# ESP-12E_Dev_Board.net
KiCad netlist of a schematic drawn in EAGLE
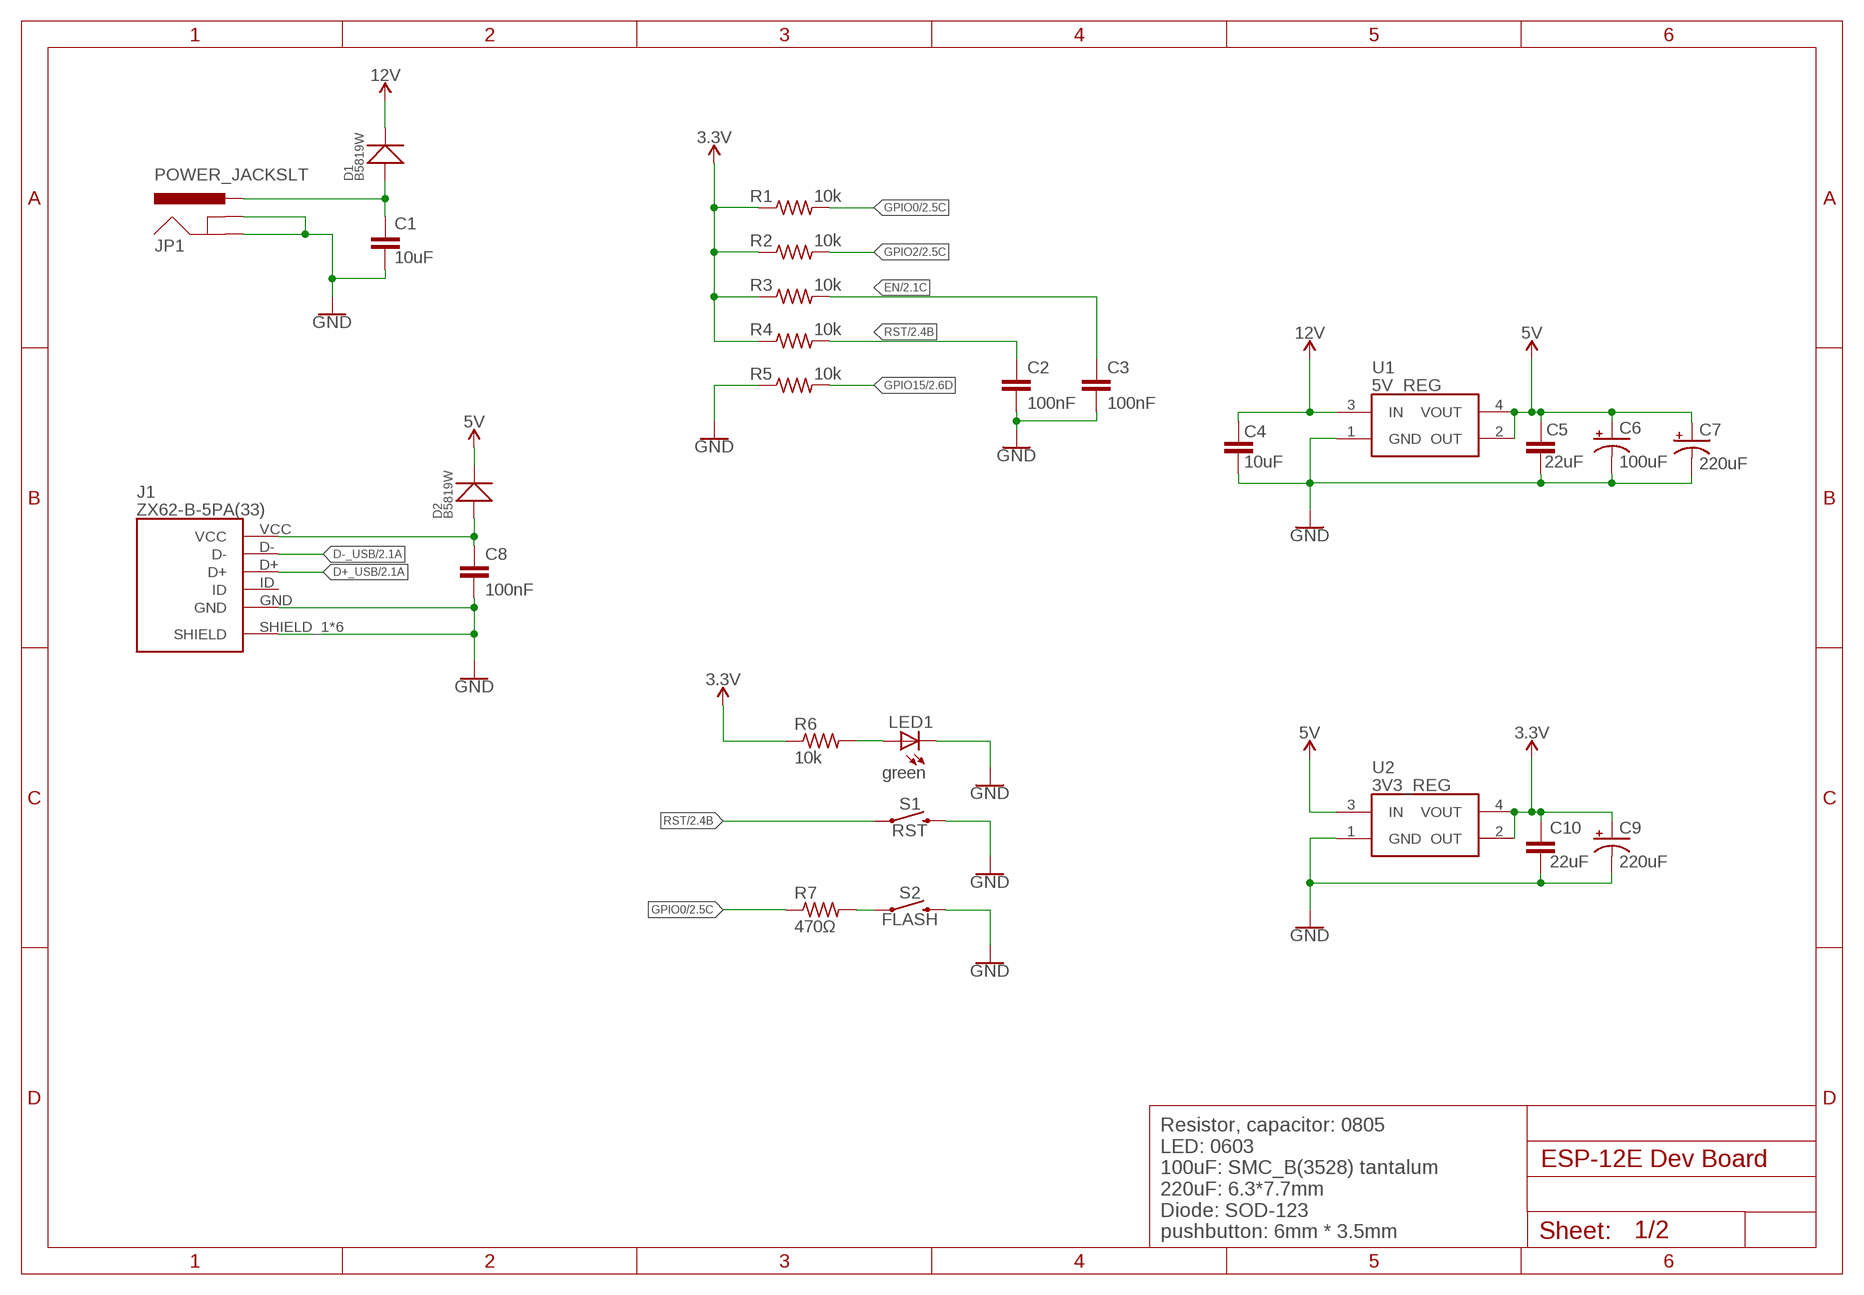
[diagram p0: schematic, sheet 1]
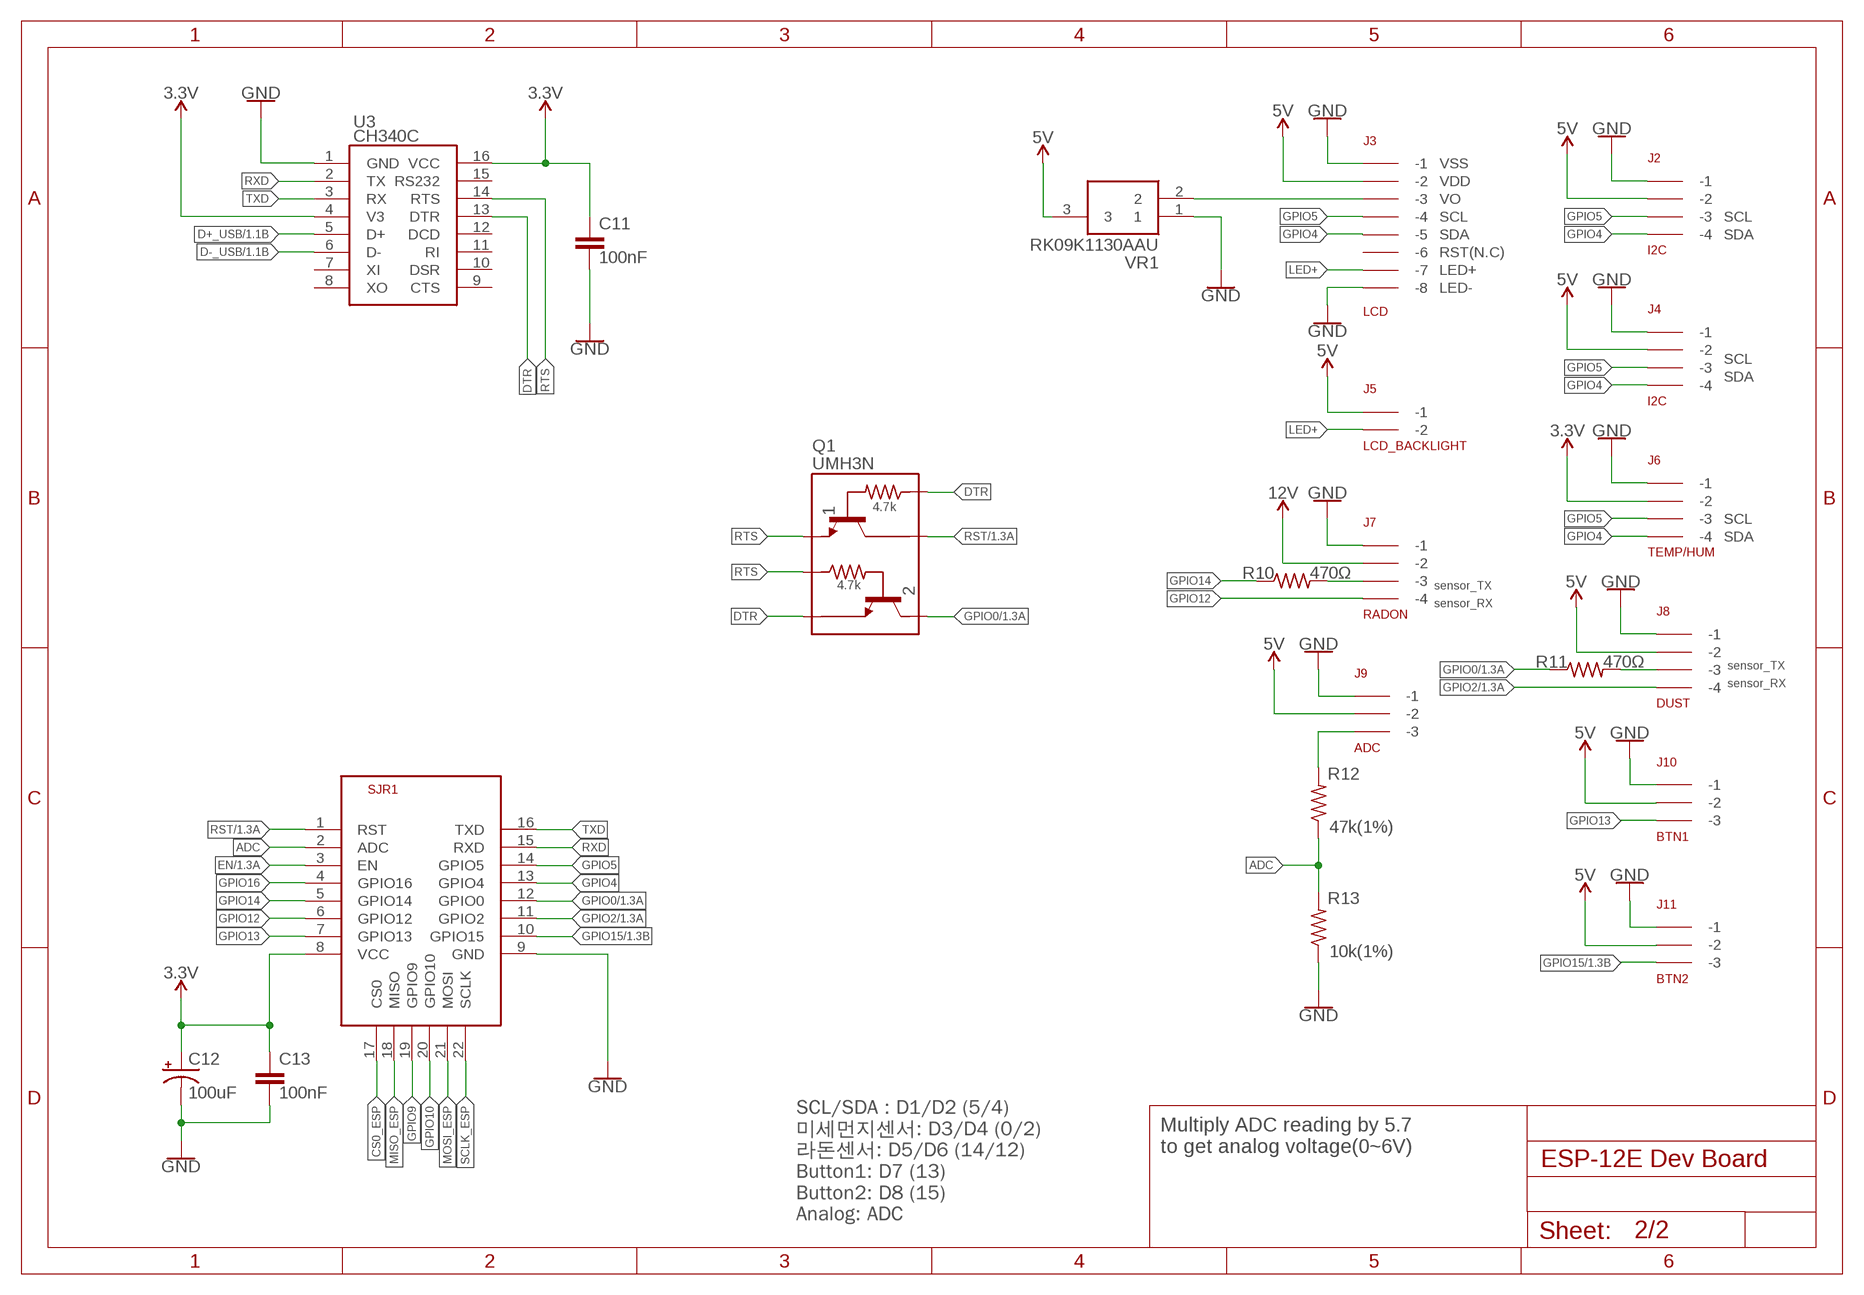
[diagram p1: schematic, sheet 2]

(export (version "E")
  (design (tool "Eeschema 10.0.6"))
  (components
    (comp (ref "C1")
      (value "10uF")
      (footprint "eagle-import:C0805")
      (libsource (lib "eagle-import") (part "C-EUC0805"))
    )
    (comp (ref "C2")
      (value "100nF")
      (footprint "eagle-import:C0805")
      (libsource (lib "eagle-import") (part "C-EUC0805"))
    )
    (comp (ref "C3")
      (value "100nF")
      (footprint "eagle-import:C0805")
      (libsource (lib "eagle-import") (part "C-EUC0805"))
    )
    (comp (ref "C4")
      (value "10uF")
      (footprint "eagle-import:C0805")
      (libsource (lib "eagle-import") (part "C-EUC0805"))
    )
    (comp (ref "C5")
      (value "22uF")
      (footprint "eagle-import:C0805")
      (libsource (lib "eagle-import") (part "C-EUC0805"))
    )
    (comp (ref "C6")
      (value "100uF")
      (footprint "eagle-import:SMC_B")
      (libsource (lib "eagle-import") (part "CPOL-USSMCB"))
    )
    (comp (ref "C7")
      (value "220uF")
      (footprint "eagle-import:UD-6,3X7,7_NICHICON")
      (libsource (lib "eagle-import") (part "CPOL-USUD-6,3X7,7"))
    )
    (comp (ref "C8")
      (value "100nF")
      (footprint "eagle-import:C0805")
      (libsource (lib "eagle-import") (part "C-EUC0805"))
    )
    (comp (ref "C9")
      (value "220uF")
      (footprint "eagle-import:UD-6,3X7,7_NICHICON")
      (libsource (lib "eagle-import") (part "CPOL-USUD-6,3X7,7"))
    )
    (comp (ref "C10")
      (value "22uF")
      (footprint "eagle-import:C0805")
      (libsource (lib "eagle-import") (part "C-EUC0805"))
    )
    (comp (ref "D1")
      (value "B5819W")
      (footprint "eagle-import:SOD-123")
      (fields (field (name "MPN") "SS0520-7-F"))
      (libsource (lib "eagle-import") (part "SMD-DIODE-SCHOTTKY-20V-500MA(SOD-123)"))
    )
    (comp (ref "D2")
      (value "B5819W")
      (footprint "eagle-import:SOD-123")
      (fields (field (name "MPN") "SS0520-7-F"))
      (libsource (lib "eagle-import") (part "SMD-DIODE-SCHOTTKY-20V-500MA(SOD-123)"))
    )
    (comp (ref "J1")
      (value "ZX62-B-5PA(33)")
      (footprint "eagle-import:ZX62B5PA33")
      (fields (field (name "MOUSER_PART_NUMBER") "798-ZX62-B-5PA33"))
      (libsource (lib "eagle-import") (part "ZX62-B-5PA(33)"))
    )
    (comp (ref "JP1")
      (value "POWER_JACKSLT")
      (footprint "eagle-import:POWER_JACK_SLOT")
      (libsource (lib "eagle-import") (part "POWER_JACKSLT"))
    )
    (comp (ref "LED1")
      (value "green")
      (footprint "eagle-import:CHIP-LED0603")
      (libsource (lib "eagle-import") (part "LEDCHIP-LED0603"))
    )
    (comp (ref "R1")
      (value "10k")
      (footprint "eagle-import:R0805")
      (libsource (lib "eagle-import") (part "R-US_R0805"))
    )
    (comp (ref "R2")
      (value "10k")
      (footprint "eagle-import:R0805")
      (libsource (lib "eagle-import") (part "R-US_R0805"))
    )
    (comp (ref "R3")
      (value "10k")
      (footprint "eagle-import:R0805")
      (libsource (lib "eagle-import") (part "R-US_R0805"))
    )
    (comp (ref "R4")
      (value "10k")
      (footprint "eagle-import:R0805")
      (libsource (lib "eagle-import") (part "R-US_R0805"))
    )
    (comp (ref "R5")
      (value "10k")
      (footprint "eagle-import:R0805")
      (libsource (lib "eagle-import") (part "R-US_R0805"))
    )
    (comp (ref "R6")
      (value "10k")
      (footprint "eagle-import:R0805")
      (libsource (lib "eagle-import") (part "R-US_R0805"))
    )
    (comp (ref "R7")
      (value "470Ω")
      (footprint "eagle-import:R0805")
      (libsource (lib "eagle-import") (part "R-US_R0805"))
    )
    (comp (ref "S1")
      (value "RST")
      (footprint "eagle-import:TACTILE_SWITCH_SMD_6.0X3.5MM")
      (libsource (lib "eagle-import") (part "MOMENTARY-SWITCH-SPST-SMD-6.0X3.5MM"))
    )
    (comp (ref "S2")
      (value "FLASH")
      (footprint "eagle-import:TACTILE_SWITCH_SMD_6.0X3.5MM")
      (libsource (lib "eagle-import") (part "MOMENTARY-SWITCH-SPST-SMD-6.0X3.5MM"))
    )
    (comp (ref "U1")
      (value "5V_REG")
      (footprint "eagle-import:SOT230P700X170-4N")
      (fields
        (field (name "MANUFACTURER_PART_NUMBER") "AZ1117H-5.0TRE1")
        (field (name "MOUSER_PART_NUMBER") "621-AZ1117H-5.0TRE1")
      )
      (libsource (lib "eagle-import") (part "AZ1117H-5.0TRE1"))
    )
    (comp (ref "U2")
      (value "3V3_REG")
      (footprint "eagle-import:SOT230P700X170-4N")
      (fields
        (field (name "MANUFACTURER_PART_NUMBER") "AZ1117H-5.0TRE1")
        (field (name "MOUSER_PART_NUMBER") "621-AZ1117H-5.0TRE1")
      )
      (libsource (lib "eagle-import") (part "AZ1117H-5.0TRE1"))
    )
    (comp (ref "C11")
      (value "100nF")
      (footprint "eagle-import:C0805")
      (libsource (lib "eagle-import") (part "C-EUC0805"))
    )
    (comp (ref "C12")
      (value "100uF")
      (footprint "eagle-import:SMC_B")
      (libsource (lib "eagle-import") (part "CPOL-USSMCB"))
    )
    (comp (ref "C13")
      (value "100nF")
      (footprint "eagle-import:C0805")
      (libsource (lib "eagle-import") (part "C-EUC0805"))
    )
    (comp (ref "J2")
      (value "I2C")
      (footprint "eagle-import:5267-4")
      (libsource (lib "eagle-import") (part "5267-4"))
    )
    (comp (ref "J3")
      (value "LCD")
      (footprint "eagle-import:5267-8")
      (libsource (lib "eagle-import") (part "5267-8"))
    )
    (comp (ref "J4")
      (value "I2C")
      (footprint "eagle-import:5267-4")
      (libsource (lib "eagle-import") (part "5267-4"))
    )
    (comp (ref "J5")
      (value "LCD_BACKLIGHT")
      (footprint "eagle-import:5267-2")
      (libsource (lib "eagle-import") (part "5267-2"))
    )
    (comp (ref "J6")
      (value "TEMP/HUM")
      (footprint "eagle-import:5267-4")
      (libsource (lib "eagle-import") (part "5267-4"))
    )
    (comp (ref "J7")
      (value "RADON")
      (footprint "eagle-import:5267-4")
      (libsource (lib "eagle-import") (part "5267-4"))
    )
    (comp (ref "J8")
      (value "DUST")
      (footprint "eagle-import:5267-4")
      (libsource (lib "eagle-import") (part "5267-4"))
    )
    (comp (ref "J9")
      (value "ADC")
      (footprint "eagle-import:5267-3")
      (libsource (lib "eagle-import") (part "5267-3"))
    )
    (comp (ref "J10")
      (value "BTN1")
      (footprint "eagle-import:5267-3")
      (libsource (lib "eagle-import") (part "5267-3"))
    )
    (comp (ref "J11")
      (value "BTN2")
      (footprint "eagle-import:5267-3")
      (libsource (lib "eagle-import") (part "5267-3"))
    )
    (comp (ref "Q1")
      (value "UMH3N")
      (footprint "eagle-import:SOT65P210X100-6N")
      (fields
        (field (name "MANUFACTURER_PART_NUMBER") "UMH3NFHATN")
        (field (name "MOUSER_PART_NUMBER") "755-UMH3NFHATN")
      )
      (libsource (lib "eagle-import") (part "UMH3NFHATN"))
    )
    (comp (ref "R10")
      (value "470Ω")
      (footprint "eagle-import:R0805")
      (libsource (lib "eagle-import") (part "R-US_R0805"))
    )
    (comp (ref "R11")
      (value "470Ω")
      (footprint "eagle-import:R0805")
      (libsource (lib "eagle-import") (part "R-US_R0805"))
    )
    (comp (ref "R12")
      (value "47k(1%)")
      (footprint "eagle-import:R0805")
      (libsource (lib "eagle-import") (part "R-US_R0805"))
    )
    (comp (ref "R13")
      (value "10k(1%)")
      (footprint "eagle-import:R0805")
      (libsource (lib "eagle-import") (part "R-US_R0805"))
    )
    (comp (ref "SJR1")
      (value "ESP-12E")
      (footprint "eagle-import:ESP8266-ESP12E")
      (libsource (lib "eagle-import") (part "ESP8266-12EESP12E"))
    )
    (comp (ref "U3")
      (value "CH340C")
      (footprint "eagle-import:SOIC16")
      (libsource (lib "eagle-import") (part "CH340G"))
    )
    (comp (ref "VR1")
      (value "RK09K1130AAU")
      (footprint "eagle-import:RK09K1130BGM")
      (fields
        (field (name "MANUFACTURER_PART_NUMBER") "RK09K1130A6S")
        (field (name "MOUSER_PART_NUMBER") "688-RK09K1130A6S")
      )
      (libsource (lib "eagle-import") (part "RK09K1130A6S"))
    )
  )
  (nets
    (net (code "1") (name "3.3V") (class "Default")
      (node (ref "C10") (pin "2") (pinfunction "2_2") (pintype "passive"))
      (node (ref "C11") (pin "2") (pinfunction "2_2") (pintype "passive"))
      (node (ref "C12") (pin "+") (pinfunction "+_+") (pintype "passive"))
      (node (ref "C13") (pin "2") (pinfunction "2_2") (pintype "passive"))
      (node (ref "C9") (pin "+") (pinfunction "+_+") (pintype "passive"))
      (node (ref "J6") (pin "P$2") (pinfunction "-2_P$2") (pintype "bidirectional"))
      (node (ref "R1") (pin "1") (pinfunction "1_1") (pintype "passive"))
      (node (ref "R2") (pin "1") (pinfunction "1_1") (pintype "passive"))
      (node (ref "R3") (pin "1") (pinfunction "1_1") (pintype "passive"))
      (node (ref "R4") (pin "1") (pinfunction "1_1") (pintype "passive"))
      (node (ref "R6") (pin "1") (pinfunction "1_1") (pintype "passive"))
      (node (ref "SJR1") (pin "8") (pinfunction "VCC_8") (pintype "bidirectional"))
      (node (ref "U2") (pin "2") (pinfunction "OUT_2") (pintype "bidirectional"))
      (node (ref "U2") (pin "4") (pinfunction "VOUT_4") (pintype "bidirectional"))
      (node (ref "U3") (pin "16") (pinfunction "VCC_16") (pintype "bidirectional"))
      (node (ref "U3") (pin "4") (pinfunction "V3_4") (pintype "bidirectional"))
    )
    (net (code "2") (name "5V") (class "Default")
      (node (ref "C5") (pin "1") (pinfunction "1_1") (pintype "passive"))
      (node (ref "C6") (pin "+") (pinfunction "+_+") (pintype "passive"))
      (node (ref "C7") (pin "+") (pinfunction "+_+") (pintype "passive"))
      (node (ref "D2") (pin "-") (pinfunction "-_-") (pintype "passive"))
      (node (ref "J10") (pin "P$2") (pinfunction "-2_P$2") (pintype "bidirectional"))
      (node (ref "J11") (pin "P$2") (pinfunction "-2_P$2") (pintype "bidirectional"))
      (node (ref "J2") (pin "P$2") (pinfunction "-2_P$2") (pintype "bidirectional"))
      (node (ref "J3") (pin "P$2") (pinfunction "-2_P$2") (pintype "bidirectional"))
      (node (ref "J4") (pin "P$2") (pinfunction "-2_P$2") (pintype "bidirectional"))
      (node (ref "J5") (pin "P$1") (pinfunction "-1_P$1") (pintype "bidirectional"))
      (node (ref "J8") (pin "P$2") (pinfunction "-2_P$2") (pintype "bidirectional"))
      (node (ref "J9") (pin "P$2") (pinfunction "-2_P$2") (pintype "bidirectional"))
      (node (ref "U1") (pin "2") (pinfunction "OUT_2") (pintype "bidirectional"))
      (node (ref "U1") (pin "4") (pinfunction "VOUT_4") (pintype "bidirectional"))
      (node (ref "U2") (pin "3") (pinfunction "IN_3") (pintype "bidirectional"))
      (node (ref "VR1") (pin "3") (pinfunction "3_3") (pintype "bidirectional"))
    )
    (net (code "3") (name "12V") (class "Default")
      (node (ref "C4") (pin "1") (pinfunction "1_1") (pintype "passive"))
      (node (ref "D1") (pin "-") (pinfunction "-_-") (pintype "passive"))
      (node (ref "J7") (pin "P$2") (pinfunction "-2_P$2") (pintype "bidirectional"))
      (node (ref "U1") (pin "3") (pinfunction "IN_3") (pintype "bidirectional"))
    )
    (net (code "4") (name "ADC") (class "Default")
      (node (ref "R12") (pin "1") (pinfunction "1_1") (pintype "passive"))
      (node (ref "R13") (pin "2") (pinfunction "2_2") (pintype "passive"))
      (node (ref "SJR1") (pin "2") (pinfunction "ADC_2") (pintype "bidirectional"))
    )
    (net (code "5") (name "CS0_ESP") (class "Default")
      (node (ref "SJR1") (pin "17") (pinfunction "CS0_17") (pintype "bidirectional"))
    )
    (net (code "6") (name "D+_USB") (class "Default")
      (node (ref "J1") (pin "D+") (pinfunction "D+_D+") (pintype "bidirectional"))
      (node (ref "U3") (pin "5") (pinfunction "D+_5") (pintype "bidirectional"))
    )
    (net (code "7") (name "D-_USB") (class "Default")
      (node (ref "J1") (pin "D-") (pinfunction "D-_D-") (pintype "bidirectional"))
      (node (ref "U3") (pin "6") (pinfunction "D-_6") (pintype "bidirectional"))
    )
    (net (code "8") (name "DTR") (class "Default")
      (node (ref "Q1") (pin "2") (pinfunction "2_2") (pintype "bidirectional"))
      (node (ref "Q1") (pin "4") (pinfunction "4_4") (pintype "bidirectional"))
      (node (ref "U3") (pin "13") (pinfunction "DTR_13") (pintype "bidirectional"))
    )
    (net (code "9") (name "EN") (class "Default")
      (node (ref "C3") (pin "2") (pinfunction "2_2") (pintype "passive"))
      (node (ref "R3") (pin "2") (pinfunction "2_2") (pintype "passive"))
      (node (ref "SJR1") (pin "3") (pinfunction "EN_3") (pintype "bidirectional"))
    )
    (net (code "10") (name "GND") (class "Default")
      (node (ref "C1") (pin "1") (pinfunction "1_1") (pintype "passive"))
      (node (ref "C10") (pin "1") (pinfunction "1_1") (pintype "passive"))
      (node (ref "C11") (pin "1") (pinfunction "1_1") (pintype "passive"))
      (node (ref "C12") (pin "-") (pinfunction "-_-") (pintype "passive"))
      (node (ref "C13") (pin "1") (pinfunction "1_1") (pintype "passive"))
      (node (ref "C2") (pin "1") (pinfunction "1_1") (pintype "passive"))
      (node (ref "C3") (pin "1") (pinfunction "1_1") (pintype "passive"))
      (node (ref "C4") (pin "2") (pinfunction "2_2") (pintype "passive"))
      (node (ref "C5") (pin "2") (pinfunction "2_2") (pintype "passive"))
      (node (ref "C6") (pin "-") (pinfunction "-_-") (pintype "passive"))
      (node (ref "C7") (pin "-") (pinfunction "-_-") (pintype "passive"))
      (node (ref "C8") (pin "1") (pinfunction "1_1") (pintype "passive"))
      (node (ref "C9") (pin "-") (pinfunction "-_-") (pintype "passive"))
      (node (ref "J1") (pin "GND") (pinfunction "GND_GND") (pintype "bidirectional"))
      (node (ref "J1") (pin "SHIELD_1") (pinfunction "SHIELD_SHIELD_1") (pintype "bidirectional"))
      (node (ref "J1") (pin "SHIELD_2") (pinfunction "SHIELD_SHIELD_2") (pintype "bidirectional"))
      (node (ref "J1") (pin "SHIELD_3") (pinfunction "SHIELD_SHIELD_3") (pintype "bidirectional"))
      (node (ref "J1") (pin "SHIELD_4") (pinfunction "SHIELD_SHIELD_4") (pintype "bidirectional"))
      (node (ref "J1") (pin "SHIELD_5") (pinfunction "SHIELD_SHIELD_5") (pintype "bidirectional"))
      (node (ref "J1") (pin "SHIELD_6") (pinfunction "SHIELD_SHIELD_6") (pintype "bidirectional"))
      (node (ref "J10") (pin "P$1") (pinfunction "-1_P$1") (pintype "bidirectional"))
      (node (ref "J11") (pin "P$1") (pinfunction "-1_P$1") (pintype "bidirectional"))
      (node (ref "J2") (pin "P$1") (pinfunction "-1_P$1") (pintype "bidirectional"))
      (node (ref "J3") (pin "P$1") (pinfunction "-1_P$1") (pintype "bidirectional"))
      (node (ref "J3") (pin "P$8") (pinfunction "-8_P$8") (pintype "bidirectional"))
      (node (ref "J4") (pin "P$1") (pinfunction "-1_P$1") (pintype "bidirectional"))
      (node (ref "J6") (pin "P$1") (pinfunction "-1_P$1") (pintype "bidirectional"))
      (node (ref "J7") (pin "P$1") (pinfunction "-1_P$1") (pintype "bidirectional"))
      (node (ref "J8") (pin "P$1") (pinfunction "-1_P$1") (pintype "bidirectional"))
      (node (ref "J9") (pin "P$1") (pinfunction "-1_P$1") (pintype "bidirectional"))
      (node (ref "JP1") (pin "GND@1") (pinfunction "GNDBREAK_GND@1") (pintype "power_in"))
      (node (ref "JP1") (pin "GND@2") (pinfunction "GND_GND@2") (pintype "power_in"))
      (node (ref "LED1") (pin "C") (pinfunction "C_C") (pintype "passive"))
      (node (ref "R13") (pin "1") (pinfunction "1_1") (pintype "passive"))
      (node (ref "R5") (pin "1") (pinfunction "1_1") (pintype "passive"))
      (node (ref "S1") (pin "2") (pinfunction "2_2") (pintype "passive"))
      (node (ref "S2") (pin "2") (pinfunction "2_2") (pintype "passive"))
      (node (ref "SJR1") (pin "9") (pinfunction "GND_9") (pintype "bidirectional"))
      (node (ref "U1") (pin "1") (pinfunction "GND_1") (pintype "bidirectional"))
      (node (ref "U2") (pin "1") (pinfunction "GND_1") (pintype "bidirectional"))
      (node (ref "U3") (pin "1") (pinfunction "GND_1") (pintype "bidirectional"))
      (node (ref "VR1") (pin "1") (pinfunction "1_1") (pintype "bidirectional"))
    )
    (net (code "11") (name "GPIO0") (class "Default")
      (node (ref "Q1") (pin "3") (pinfunction "3_3") (pintype "bidirectional"))
      (node (ref "R1") (pin "2") (pinfunction "2_2") (pintype "passive"))
      (node (ref "R11") (pin "1") (pinfunction "1_1") (pintype "passive"))
      (node (ref "R7") (pin "1") (pinfunction "1_1") (pintype "passive"))
      (node (ref "SJR1") (pin "12") (pinfunction "GPIO0_12") (pintype "bidirectional"))
    )
    (net (code "12") (name "GPIO2") (class "Default")
      (node (ref "J8") (pin "P$4") (pinfunction "-4_P$4") (pintype "bidirectional"))
      (node (ref "R2") (pin "2") (pinfunction "2_2") (pintype "passive"))
      (node (ref "SJR1") (pin "11") (pinfunction "GPIO2_11") (pintype "bidirectional"))
    )
    (net (code "13") (name "GPIO4") (class "Default")
      (node (ref "J2") (pin "P$4") (pinfunction "-4_P$4") (pintype "bidirectional"))
      (node (ref "J3") (pin "P$5") (pinfunction "-5_P$5") (pintype "bidirectional"))
      (node (ref "J4") (pin "P$4") (pinfunction "-4_P$4") (pintype "bidirectional"))
      (node (ref "J6") (pin "P$4") (pinfunction "-4_P$4") (pintype "bidirectional"))
      (node (ref "SJR1") (pin "13") (pinfunction "GPIO4_13") (pintype "bidirectional"))
    )
    (net (code "14") (name "GPIO5") (class "Default")
      (node (ref "J2") (pin "P$3") (pinfunction "-3_P$3") (pintype "bidirectional"))
      (node (ref "J3") (pin "P$4") (pinfunction "-4_P$4") (pintype "bidirectional"))
      (node (ref "J4") (pin "P$3") (pinfunction "-3_P$3") (pintype "bidirectional"))
      (node (ref "J6") (pin "P$3") (pinfunction "-3_P$3") (pintype "bidirectional"))
      (node (ref "SJR1") (pin "14") (pinfunction "GPIO5_14") (pintype "bidirectional"))
    )
    (net (code "15") (name "GPIO9") (class "Default")
      (node (ref "SJR1") (pin "19") (pinfunction "GPIO9_19") (pintype "bidirectional"))
    )
    (net (code "16") (name "GPIO10") (class "Default")
      (node (ref "SJR1") (pin "20") (pinfunction "GPIO10_20") (pintype "bidirectional"))
    )
    (net (code "17") (name "GPIO12") (class "Default")
      (node (ref "J7") (pin "P$4") (pinfunction "-4_P$4") (pintype "bidirectional"))
      (node (ref "SJR1") (pin "6") (pinfunction "GPIO12_6") (pintype "bidirectional"))
    )
    (net (code "18") (name "GPIO13") (class "Default")
      (node (ref "J10") (pin "P$3") (pinfunction "-3_P$3") (pintype "bidirectional"))
      (node (ref "SJR1") (pin "7") (pinfunction "GPIO13_7") (pintype "bidirectional"))
    )
    (net (code "19") (name "GPIO14") (class "Default")
      (node (ref "R10") (pin "1") (pinfunction "1_1") (pintype "passive"))
      (node (ref "SJR1") (pin "5") (pinfunction "GPIO14_5") (pintype "bidirectional"))
    )
    (net (code "20") (name "GPIO15") (class "Default")
      (node (ref "J11") (pin "P$3") (pinfunction "-3_P$3") (pintype "bidirectional"))
      (node (ref "R5") (pin "2") (pinfunction "2_2") (pintype "passive"))
      (node (ref "SJR1") (pin "10") (pinfunction "GPIO15_10") (pintype "bidirectional"))
    )
    (net (code "21") (name "GPIO16") (class "Default")
      (node (ref "SJR1") (pin "4") (pinfunction "GPIO16_4") (pintype "bidirectional"))
    )
    (net (code "22") (name "LED+") (class "Default")
      (node (ref "J3") (pin "P$7") (pinfunction "-7_P$7") (pintype "bidirectional"))
      (node (ref "J5") (pin "P$2") (pinfunction "-2_P$2") (pintype "bidirectional"))
    )
    (net (code "23") (name "MISO_ESP") (class "Default")
      (node (ref "SJR1") (pin "18") (pinfunction "MISO_18") (pintype "bidirectional"))
    )
    (net (code "24") (name "MOSI_ESP") (class "Default")
      (node (ref "SJR1") (pin "21") (pinfunction "MOSI_21") (pintype "bidirectional"))
    )
    (net (code "25") (name "Net-(C1-Pad2)") (class "Default")
      (node (ref "C1") (pin "2") (pinfunction "2_2") (pintype "passive"))
      (node (ref "D1") (pin "+") (pinfunction "+_+") (pintype "passive"))
      (node (ref "JP1") (pin "PWR") (pinfunction "PWR_PWR") (pintype "power_in"))
    )
    (net (code "26") (name "Net-(C8-Pad2)") (class "Default")
      (node (ref "C8") (pin "2") (pinfunction "2_2") (pintype "passive"))
      (node (ref "D2") (pin "+") (pinfunction "+_+") (pintype "passive"))
      (node (ref "J1") (pin "VCC") (pinfunction "VCC_VCC") (pintype "bidirectional"))
    )
    (net (code "27") (name "Net-(J3--3)") (class "Default")
      (node (ref "J3") (pin "P$3") (pinfunction "-3_P$3") (pintype "bidirectional"))
      (node (ref "VR1") (pin "2") (pinfunction "2_2") (pintype "bidirectional"))
    )
    (net (code "28") (name "Net-(J7--3)") (class "Default")
      (node (ref "J7") (pin "P$3") (pinfunction "-3_P$3") (pintype "bidirectional"))
      (node (ref "R10") (pin "2") (pinfunction "2_2") (pintype "passive"))
    )
    (net (code "29") (name "Net-(J8--3)") (class "Default")
      (node (ref "J8") (pin "P$3") (pinfunction "-3_P$3") (pintype "bidirectional"))
      (node (ref "R11") (pin "2") (pinfunction "2_2") (pintype "passive"))
    )
    (net (code "30") (name "Net-(J9--3)") (class "Default")
      (node (ref "J9") (pin "P$3") (pinfunction "-3_P$3") (pintype "bidirectional"))
      (node (ref "R12") (pin "2") (pinfunction "2_2") (pintype "passive"))
    )
    (net (code "31") (name "Net-(LED1-PadA)") (class "Default")
      (node (ref "LED1") (pin "A") (pinfunction "A_A") (pintype "passive"))
      (node (ref "R6") (pin "2") (pinfunction "2_2") (pintype "passive"))
    )
    (net (code "32") (name "Net-(R7-Pad2)") (class "Default")
      (node (ref "R7") (pin "2") (pinfunction "2_2") (pintype "passive"))
      (node (ref "S2") (pin "1") (pinfunction "1_1") (pintype "passive"))
    )
    (net (code "33") (name "RST") (class "Default")
      (node (ref "C2") (pin "2") (pinfunction "2_2") (pintype "passive"))
      (node (ref "Q1") (pin "6") (pinfunction "6_6") (pintype "bidirectional"))
      (node (ref "R4") (pin "2") (pinfunction "2_2") (pintype "passive"))
      (node (ref "S1") (pin "1") (pinfunction "1_1") (pintype "passive"))
      (node (ref "SJR1") (pin "1") (pinfunction "RST_1") (pintype "bidirectional"))
    )
    (net (code "34") (name "RTS") (class "Default")
      (node (ref "Q1") (pin "1") (pinfunction "1_1") (pintype "bidirectional"))
      (node (ref "Q1") (pin "5") (pinfunction "5_5") (pintype "bidirectional"))
      (node (ref "U3") (pin "14") (pinfunction "RTS_14") (pintype "bidirectional"))
    )
    (net (code "35") (name "RXD") (class "Default")
      (node (ref "SJR1") (pin "15") (pinfunction "RXD_15") (pintype "bidirectional"))
      (node (ref "U3") (pin "2") (pinfunction "TX_2") (pintype "bidirectional"))
    )
    (net (code "36") (name "SCLK_ESP") (class "Default")
      (node (ref "SJR1") (pin "22") (pinfunction "SCLK_22") (pintype "bidirectional"))
    )
    (net (code "37") (name "TXD") (class "Default")
      (node (ref "SJR1") (pin "16") (pinfunction "TXD_16") (pintype "bidirectional"))
      (node (ref "U3") (pin "3") (pinfunction "RX_3") (pintype "bidirectional"))
    )
    (net (code "38") (name "unconnected-(J1-PadID)") (class "Default")
      (node (ref "J1") (pin "ID") (pinfunction "ID_ID") (pintype "bidirectional"))
    )
    (net (code "39") (name "unconnected-(J3--6-PadP$6)") (class "Default")
      (node (ref "J3") (pin "P$6") (pinfunction "-6_P$6") (pintype "bidirectional"))
    )
    (net (code "40") (name "unconnected-(U3-CTS-Pad9)") (class "Default")
      (node (ref "U3") (pin "9") (pinfunction "CTS_9") (pintype "bidirectional"))
    )
    (net (code "41") (name "unconnected-(U3-DCD-Pad12)") (class "Default")
      (node (ref "U3") (pin "12") (pinfunction "DCD_12") (pintype "bidirectional"))
    )
    (net (code "42") (name "unconnected-(U3-DSR-Pad10)") (class "Default")
      (node (ref "U3") (pin "10") (pinfunction "DSR_10") (pintype "bidirectional"))
    )
    (net (code "43") (name "unconnected-(U3-RI-Pad11)") (class "Default")
      (node (ref "U3") (pin "11") (pinfunction "RI_11") (pintype "bidirectional"))
    )
    (net (code "44") (name "unconnected-(U3-RS232-Pad15)") (class "Default")
      (node (ref "U3") (pin "15") (pinfunction "RS232_15") (pintype "bidirectional"))
    )
    (net (code "45") (name "unconnected-(U3-XI-Pad7)") (class "Default")
      (node (ref "U3") (pin "7") (pinfunction "XI_7") (pintype "bidirectional"))
    )
    (net (code "46") (name "unconnected-(U3-XO-Pad8)") (class "Default")
      (node (ref "U3") (pin "8") (pinfunction "XO_8") (pintype "bidirectional"))
    )
  )
)
